# giao-dong-led.net
KiCad netlist of a schematic drawn in Altium Designer
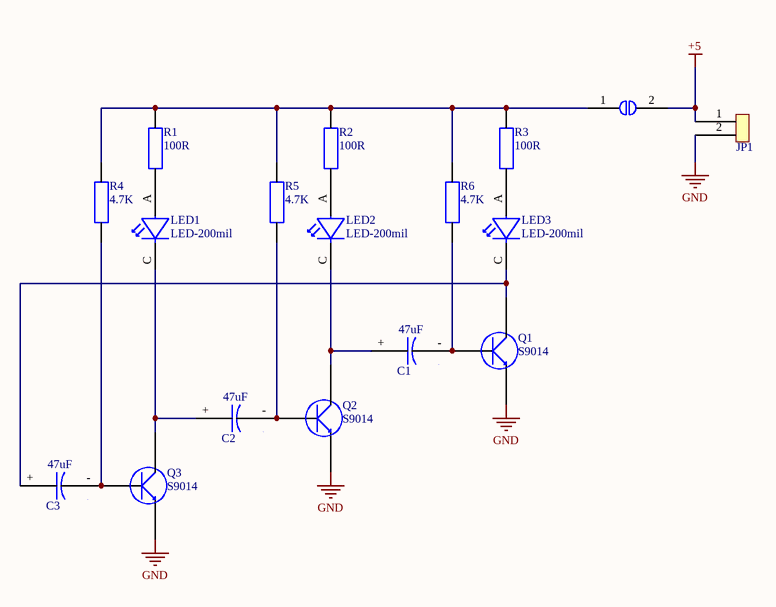
[diagram p0: giao-dong-led.SchDoc]

(export (version "E")
  (design (tool "Eeschema 10.0.6"))
  (components
    (comp (ref "C1")
      (value "47uF")
      (footprint "POL_250MIL_HORIZONTAL")
      (description "Tụ điện phân cực")
      (libsource (lib "LuongTanDat") (part "Pol-Cap"))
    )
    (comp (ref "C2")
      (value "47uF")
      (footprint "POL_250MIL_HORIZONTAL")
      (description "Tụ điện phân cực")
      (libsource (lib "LuongTanDat") (part "Pol-Cap"))
    )
    (comp (ref "C3")
      (value "47uF")
      (footprint "POL_250MIL_HORIZONTAL")
      (description "Tụ điện phân cực")
      (libsource (lib "LuongTanDat") (part "Pol-Cap"))
    )
    (comp (ref "J1")
      (value "Solderable Jump")
      (footprint "S_JP_3")
      (libsource (lib "LuongTanDat") (part "Solderable Jump"))
    )
    (comp (ref "JP1") (value "JP_2") (footprint "JP_2") (libsource (lib "LuongTanDat") (part "JP_2")))
    (comp (ref "LED1")
      (value "LED-200mil")
      (footprint "LED-200mil")
      (libsource (lib "LuongTanDat") (part "LED-200mil"))
    )
    (comp (ref "LED2")
      (value "LED-200mil")
      (footprint "LED-200mil")
      (libsource (lib "LuongTanDat") (part "LED-200mil"))
    )
    (comp (ref "LED3")
      (value "LED-200mil")
      (footprint "LED-200mil")
      (libsource (lib "LuongTanDat") (part "LED-200mil"))
    )
    (comp (ref "Q1") (value "S9014") (footprint "S9014") (libsource (lib "LuongTanDat") (part "S9014")))
    (comp (ref "Q2") (value "S9014") (footprint "S9014") (libsource (lib "LuongTanDat") (part "S9014")))
    (comp (ref "Q3") (value "S9014") (footprint "S9014") (libsource (lib "LuongTanDat") (part "S9014")))
    (comp (ref "R1")
      (value "100R")
      (footprint "RES")
      (description "điện trở size nhỏ")
      (libsource (lib "LuongTanDat") (part "RES"))
    )
    (comp (ref "R2")
      (value "100R")
      (footprint "RES")
      (description "điện trở size nhỏ")
      (libsource (lib "LuongTanDat") (part "RES"))
    )
    (comp (ref "R3")
      (value "100R")
      (footprint "RES")
      (description "điện trở size nhỏ")
      (libsource (lib "LuongTanDat") (part "RES"))
    )
    (comp (ref "R4")
      (value "4.7K")
      (footprint "RES")
      (description "điện trở size nhỏ")
      (libsource (lib "LuongTanDat") (part "RES"))
    )
    (comp (ref "R5")
      (value "4.7K")
      (footprint "RES")
      (description "điện trở size nhỏ")
      (libsource (lib "LuongTanDat") (part "RES"))
    )
    (comp (ref "R6")
      (value "4.7K")
      (footprint "RES")
      (description "điện trở size nhỏ")
      (libsource (lib "LuongTanDat") (part "RES"))
    )
  )
  (nets
    (net (code "1") (name "+5") (class "Default")
      (node (ref "J1") (pin "2") (pinfunction "2_2") (pintype "passive"))
      (node (ref "JP1") (pin "1") (pinfunction "1_1") (pintype "passive"))
    )
    (net (code "2") (name "GND") (class "Default")
      (node (ref "JP1") (pin "2") (pinfunction "2_2") (pintype "passive"))
      (node (ref "Q1") (pin "1") (pinfunction "1_1") (pintype "passive"))
      (node (ref "Q2") (pin "1") (pinfunction "1_1") (pintype "passive"))
      (node (ref "Q3") (pin "1") (pinfunction "1_1") (pintype "passive"))
    )
    (net (code "3") (name "Net-(C1-Pad-)") (class "Default")
      (node (ref "C1") (pin "-") (pintype "passive"))
      (node (ref "Q1") (pin "2") (pinfunction "2_2") (pintype "passive"))
      (node (ref "R6") (pin "1") (pinfunction "1_1") (pintype "passive"))
    )
    (net (code "4") (name "Net-(C2-Pad-)") (class "Default")
      (node (ref "C2") (pin "-") (pintype "passive"))
      (node (ref "Q2") (pin "2") (pinfunction "2_2") (pintype "passive"))
      (node (ref "R5") (pin "1") (pinfunction "1_1") (pintype "passive"))
    )
    (net (code "5") (name "Net-(C3-Pad-)") (class "Default")
      (node (ref "C3") (pin "-") (pintype "passive"))
      (node (ref "Q3") (pin "2") (pinfunction "2_2") (pintype "passive"))
      (node (ref "R4") (pin "1") (pinfunction "1_1") (pintype "passive"))
    )
    (net (code "6") (name "Net-(J1-Pad1)") (class "Default")
      (node (ref "J1") (pin "1") (pinfunction "1_1") (pintype "passive"))
      (node (ref "R1") (pin "2") (pinfunction "2_2") (pintype "passive"))
      (node (ref "R2") (pin "2") (pinfunction "2_2") (pintype "passive"))
      (node (ref "R3") (pin "2") (pinfunction "2_2") (pintype "passive"))
      (node (ref "R4") (pin "2") (pinfunction "2_2") (pintype "passive"))
      (node (ref "R5") (pin "2") (pinfunction "2_2") (pintype "passive"))
      (node (ref "R6") (pin "2") (pinfunction "2_2") (pintype "passive"))
    )
    (net (code "7") (name "Net-(LED1-1)") (class "Default")
      (node (ref "LED1") (pin "A") (pinfunction "1_A") (pintype "passive"))
      (node (ref "R1") (pin "1") (pinfunction "1_1") (pintype "passive"))
    )
    (net (code "8") (name "Net-(LED1-2)") (class "Default")
      (node (ref "C2") (pin "+") (pintype "passive"))
      (node (ref "LED1") (pin "C") (pinfunction "2_C") (pintype "passive"))
      (node (ref "Q3") (pin "3") (pinfunction "3_3") (pintype "passive"))
    )
    (net (code "9") (name "Net-(LED2-1)") (class "Default")
      (node (ref "LED2") (pin "A") (pinfunction "1_A") (pintype "passive"))
      (node (ref "R2") (pin "1") (pinfunction "1_1") (pintype "passive"))
    )
    (net (code "10") (name "Net-(LED2-2)") (class "Default")
      (node (ref "C1") (pin "+") (pintype "passive"))
      (node (ref "LED2") (pin "C") (pinfunction "2_C") (pintype "passive"))
      (node (ref "Q2") (pin "3") (pinfunction "3_3") (pintype "passive"))
    )
    (net (code "11") (name "Net-(LED3-1)") (class "Default")
      (node (ref "LED3") (pin "A") (pinfunction "1_A") (pintype "passive"))
      (node (ref "R3") (pin "1") (pinfunction "1_1") (pintype "passive"))
    )
    (net (code "12") (name "Net-(LED3-2)") (class "Default")
      (node (ref "C3") (pin "+") (pintype "passive"))
      (node (ref "LED3") (pin "C") (pinfunction "2_C") (pintype "passive"))
      (node (ref "Q1") (pin "3") (pinfunction "3_3") (pintype "passive"))
    )
  )
)
